# GBCART.net
KiCad netlist of a schematic drawn in EAGLE
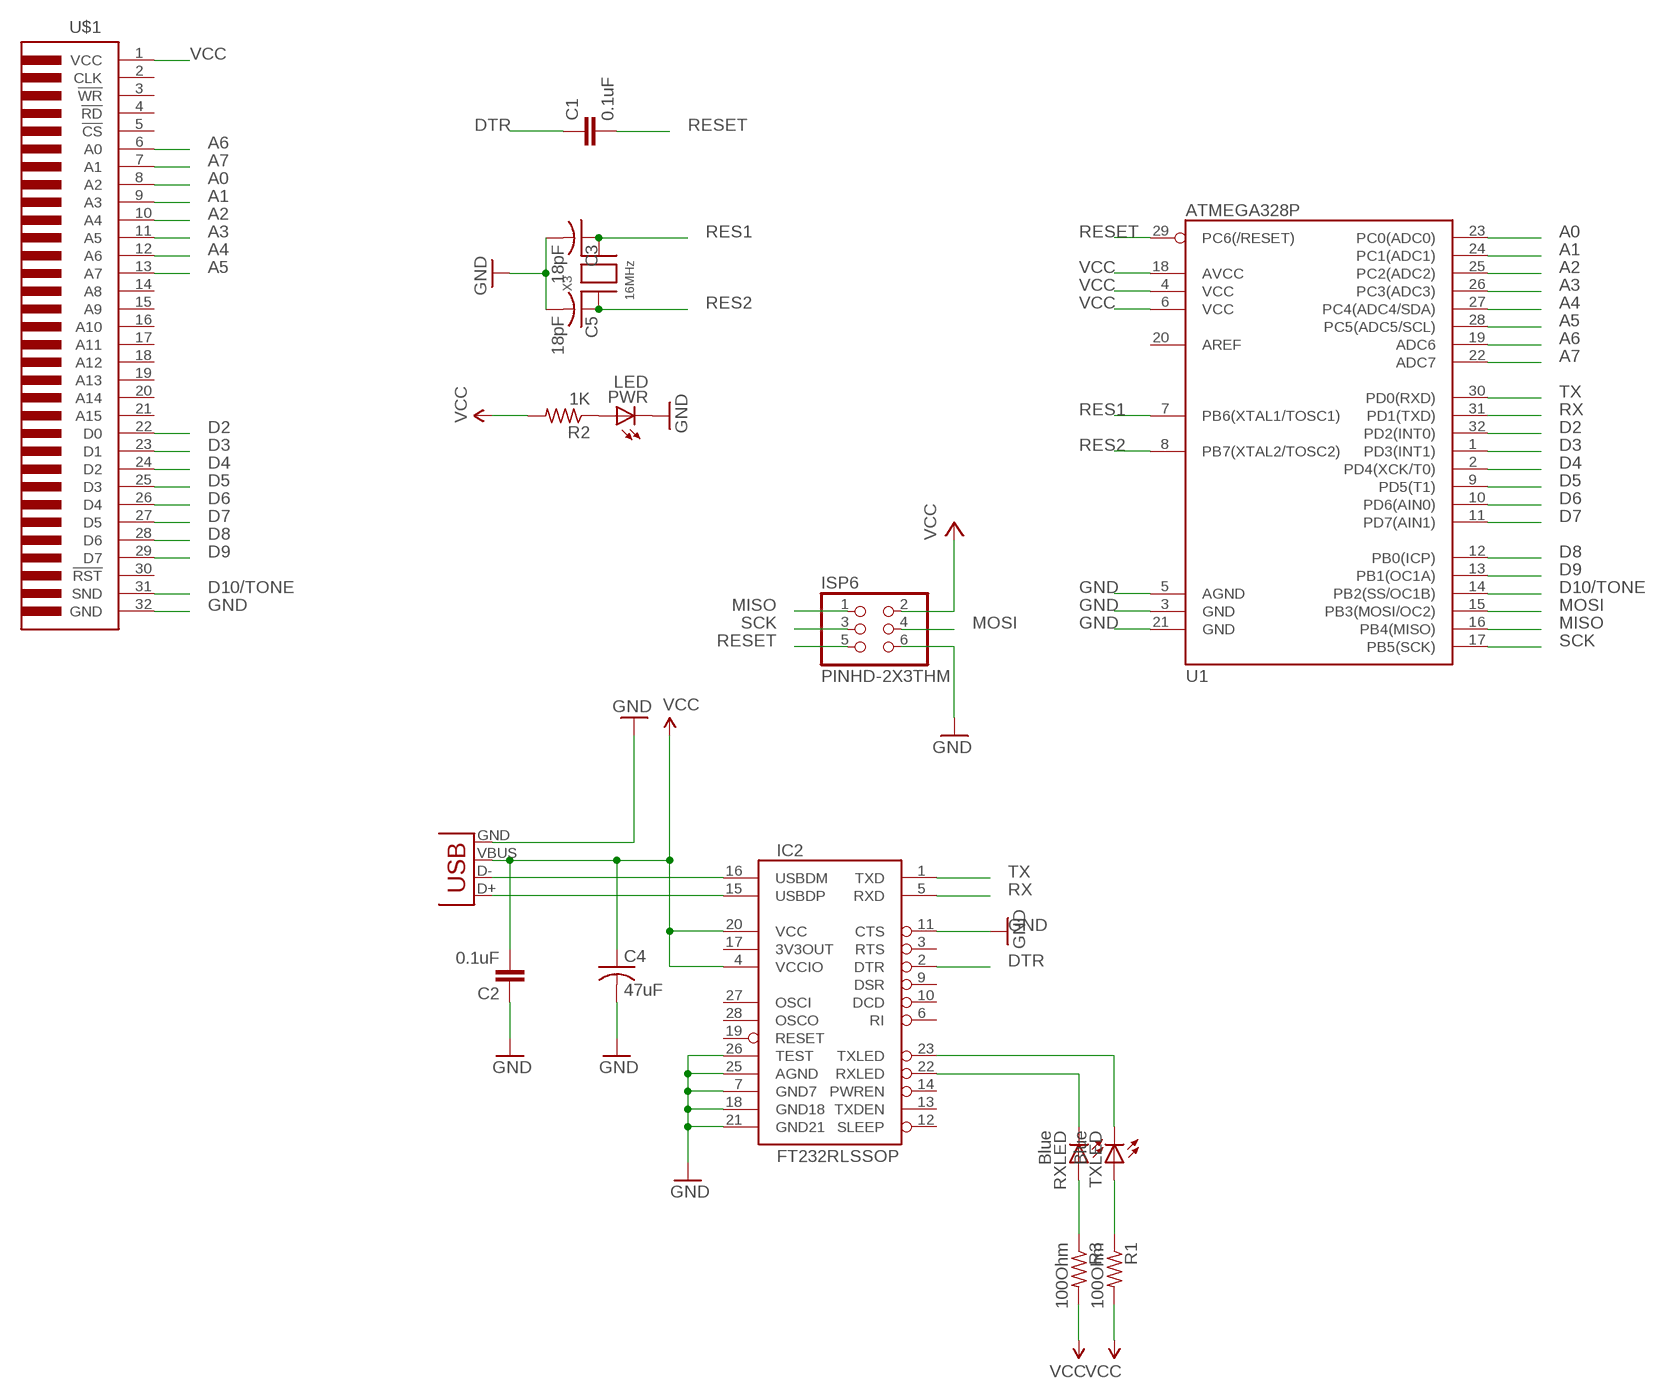
[diagram p0: schematic, sheet 1]

(export (version "E")
  (design (tool "Eeschema 10.0.6"))
  (components
    (comp (ref "C1")
      (value "0.1uF")
      (footprint "eagle-import:0805")
      (libsource (lib "eagle-import") (part "CAP0805"))
    )
    (comp (ref "C2")
      (value "0.1uF")
      (footprint "eagle-import:0805")
      (libsource (lib "eagle-import") (part "CAP0805"))
    )
    (comp (ref "C3")
      (value "18pF")
      (footprint "eagle-import:C0805K")
      (libsource (lib "eagle-import") (part "C-USC0805K"))
    )
    (comp (ref "C4")
      (value "47uF")
      (footprint "eagle-import:C0805")
      (libsource (lib "eagle-import") (part "rcl_C-USC0805"))
    )
    (comp (ref "C5")
      (value "18pF")
      (footprint "eagle-import:C0805K")
      (libsource (lib "eagle-import") (part "C-USC0805K"))
    )
    (comp (ref "IC2")
      (value "FT232RLSSOP")
      (footprint "eagle-import:SSOP28DB")
      (libsource (lib "eagle-import") (part "FT232RLSSOP"))
    )
    (comp (ref "ISP6")
      (value "PINHD-2X3THM")
      (footprint "eagle-import:ISP6")
      (libsource (lib "eagle-import") (part "PINHD-2X3THM"))
    )
    (comp (ref "PWR")
      (value "LED")
      (footprint "eagle-import:CHIPLED_0805")
      (libsource (lib "eagle-import") (part "LEDCHIPLED_0805"))
    )
    (comp (ref "R1")
      (value "100Ohm")
      (footprint "eagle-import:R0805")
      (libsource (lib "eagle-import") (part "R-US_R0805"))
    )
    (comp (ref "R2")
      (value "1K")
      (footprint "eagle-import:R0805")
      (libsource (lib "eagle-import") (part "R-US_R0805"))
    )
    (comp (ref "R3")
      (value "100Ohm")
      (footprint "eagle-import:R0805")
      (libsource (lib "eagle-import") (part "R-US_R0805"))
    )
    (comp (ref "RXLED")
      (value "Blue")
      (footprint "eagle-import:CHIPLED_0805")
      (libsource (lib "eagle-import") (part "led_LEDCHIPLED_0805"))
    )
    (comp (ref "TXLED")
      (value "Blue")
      (footprint "eagle-import:CHIPLED_0805")
      (libsource (lib "eagle-import") (part "led_LEDCHIPLED_0805"))
    )
    (comp (ref "U$1")
      (value "GBCART-FULL")
      (footprint "eagle-import:GBCART")
      (libsource (lib "eagle-import") (part "GBCART-FULL"))
    )
    (comp (ref "U1")
      (value "ATMEGA328P")
      (footprint "eagle-import:TQFP32-08")
      (libsource (lib "eagle-import") (part "ATMEGA168"))
    )
    (comp (ref "X1")
      (value "USBSMD")
      (footprint "eagle-import:USB-MINIB")
      (libsource (lib "eagle-import") (part "USBSMD"))
    )
    (comp (ref "X3")
      (value "16MHz")
      (footprint "eagle-import:NX5032")
      (libsource (lib "eagle-import") (part "XTALNX5032"))
    )
  )
  (nets
    (net (code "1") (name "/A0") (class "Default")
      (node (ref "U$1") (pin "8") (pinfunction "A2_8") (pintype "output"))
      (node (ref "U1") (pin "23") (pinfunction "PC0(ADC0)_23") (pintype "bidirectional"))
    )
    (net (code "2") (name "/A1") (class "Default")
      (node (ref "U$1") (pin "9") (pinfunction "A3_9") (pintype "output"))
      (node (ref "U1") (pin "24") (pinfunction "PC1(ADC1)_24") (pintype "bidirectional"))
    )
    (net (code "3") (name "/A2") (class "Default")
      (node (ref "U$1") (pin "10") (pinfunction "A4_10") (pintype "output"))
      (node (ref "U1") (pin "25") (pinfunction "PC2(ADC2)_25") (pintype "bidirectional"))
    )
    (net (code "4") (name "/A3") (class "Default")
      (node (ref "U$1") (pin "11") (pinfunction "A5_11") (pintype "output"))
      (node (ref "U1") (pin "26") (pinfunction "PC3(ADC3)_26") (pintype "bidirectional"))
    )
    (net (code "5") (name "/A4") (class "Default")
      (node (ref "U$1") (pin "12") (pinfunction "A6_12") (pintype "output"))
      (node (ref "U1") (pin "27") (pinfunction "PC4(ADC4/SDA)_27") (pintype "bidirectional"))
    )
    (net (code "6") (name "/A5") (class "Default")
      (node (ref "U$1") (pin "13") (pinfunction "A7_13") (pintype "output"))
      (node (ref "U1") (pin "28") (pinfunction "PC5(ADC5/SCL)_28") (pintype "bidirectional"))
    )
    (net (code "7") (name "/A6") (class "Default")
      (node (ref "U$1") (pin "6") (pinfunction "A0_6") (pintype "output"))
      (node (ref "U1") (pin "19") (pinfunction "ADC6_19") (pintype "bidirectional"))
    )
    (net (code "8") (name "/A7") (class "Default")
      (node (ref "U$1") (pin "7") (pinfunction "A1_7") (pintype "output"))
      (node (ref "U1") (pin "22") (pinfunction "ADC7_22") (pintype "bidirectional"))
    )
    (net (code "9") (name "/D2") (class "Default")
      (node (ref "U$1") (pin "22") (pinfunction "D0_22") (pintype "bidirectional"))
      (node (ref "U1") (pin "32") (pinfunction "PD2(INT0)_32") (pintype "bidirectional"))
    )
    (net (code "10") (name "/D3") (class "Default")
      (node (ref "U$1") (pin "23") (pinfunction "D1_23") (pintype "bidirectional"))
      (node (ref "U1") (pin "1") (pinfunction "PD3(INT1)_1") (pintype "bidirectional"))
    )
    (net (code "11") (name "/D4") (class "Default")
      (node (ref "U$1") (pin "24") (pinfunction "D2_24") (pintype "bidirectional"))
      (node (ref "U1") (pin "2") (pinfunction "PD4(XCK/T0)_2") (pintype "bidirectional"))
    )
    (net (code "12") (name "/D5") (class "Default")
      (node (ref "U$1") (pin "25") (pinfunction "D3_25") (pintype "bidirectional"))
      (node (ref "U1") (pin "9") (pinfunction "PD5(T1)_9") (pintype "bidirectional"))
    )
    (net (code "13") (name "/D6") (class "Default")
      (node (ref "U$1") (pin "26") (pinfunction "D4_26") (pintype "bidirectional"))
      (node (ref "U1") (pin "10") (pinfunction "PD6(AIN0)_10") (pintype "bidirectional"))
    )
    (net (code "14") (name "/D7") (class "Default")
      (node (ref "U$1") (pin "27") (pinfunction "D5_27") (pintype "bidirectional"))
      (node (ref "U1") (pin "11") (pinfunction "PD7(AIN1)_11") (pintype "bidirectional"))
    )
    (net (code "15") (name "/D8") (class "Default")
      (node (ref "U$1") (pin "28") (pinfunction "D6_28") (pintype "bidirectional"))
      (node (ref "U1") (pin "12") (pinfunction "PB0(ICP)_12") (pintype "bidirectional"))
    )
    (net (code "16") (name "/D9") (class "Default")
      (node (ref "U$1") (pin "29") (pinfunction "D7_29") (pintype "bidirectional"))
      (node (ref "U1") (pin "13") (pinfunction "PB1(OC1A)_13") (pintype "bidirectional"))
    )
    (net (code "17") (name "/D10{slash}TONE") (class "Default")
      (node (ref "U$1") (pin "31") (pinfunction "SND_31") (pintype "bidirectional"))
      (node (ref "U1") (pin "14") (pinfunction "PB2(SS/OC1B)_14") (pintype "bidirectional"))
    )
    (net (code "18") (name "/DTR") (class "Default")
      (node (ref "C1") (pin "1") (pinfunction "1_1") (pintype "passive"))
      (node (ref "IC2") (pin "2") (pinfunction "DTR_2") (pintype "output"))
    )
    (net (code "19") (name "/MISO") (class "Default")
      (node (ref "ISP6") (pin "1") (pinfunction "1_1") (pintype "passive"))
      (node (ref "U1") (pin "16") (pinfunction "PB4(MISO)_16") (pintype "bidirectional"))
    )
    (net (code "20") (name "/MOSI") (class "Default")
      (node (ref "ISP6") (pin "4") (pinfunction "4_4") (pintype "passive"))
      (node (ref "U1") (pin "15") (pinfunction "PB3(MOSI/OC2)_15") (pintype "bidirectional"))
    )
    (net (code "21") (name "/RES1") (class "Default")
      (node (ref "C3") (pin "1") (pinfunction "1_1") (pintype "passive"))
      (node (ref "U1") (pin "7") (pinfunction "PB6(XTAL1/TOSC1)_7") (pintype "bidirectional"))
      (node (ref "X3") (pin "P$2") (pinfunction "P$2_P$2") (pintype "bidirectional"))
    )
    (net (code "22") (name "/RES2") (class "Default")
      (node (ref "C5") (pin "1") (pinfunction "1_1") (pintype "passive"))
      (node (ref "U1") (pin "8") (pinfunction "PB7(XTAL2/TOSC2)_8") (pintype "bidirectional"))
      (node (ref "X3") (pin "P$1") (pinfunction "P$1_P$1") (pintype "bidirectional"))
    )
    (net (code "23") (name "/RESET") (class "Default")
      (node (ref "C1") (pin "2") (pinfunction "2_2") (pintype "passive"))
      (node (ref "ISP6") (pin "5") (pinfunction "5_5") (pintype "passive"))
      (node (ref "U1") (pin "29") (pinfunction "PC6(/RESET)_29") (pintype "bidirectional"))
    )
    (net (code "24") (name "/RX") (class "Default")
      (node (ref "IC2") (pin "5") (pinfunction "RXD_5") (pintype "input"))
      (node (ref "U1") (pin "31") (pinfunction "PD1(TXD)_31") (pintype "bidirectional"))
    )
    (net (code "25") (name "/SCK") (class "Default")
      (node (ref "ISP6") (pin "3") (pinfunction "3_3") (pintype "passive"))
      (node (ref "U1") (pin "17") (pinfunction "PB5(SCK)_17") (pintype "bidirectional"))
    )
    (net (code "26") (name "/TX") (class "Default")
      (node (ref "IC2") (pin "1") (pinfunction "TXD_1") (pintype "output"))
      (node (ref "U1") (pin "30") (pinfunction "PD0(RXD)_30") (pintype "bidirectional"))
    )
    (net (code "27") (name "GND") (class "Default")
      (node (ref "C2") (pin "1") (pinfunction "1_1") (pintype "passive"))
      (node (ref "C3") (pin "2") (pinfunction "2_2") (pintype "passive"))
      (node (ref "C4") (pin "2") (pinfunction "2_2") (pintype "passive"))
      (node (ref "C5") (pin "2") (pinfunction "2_2") (pintype "passive"))
      (node (ref "IC2") (pin "11") (pinfunction "CTS_11") (pintype "input"))
      (node (ref "IC2") (pin "18") (pinfunction "GND18_18") (pintype "power_in"))
      (node (ref "IC2") (pin "21") (pinfunction "GND21_21") (pintype "power_in"))
      (node (ref "IC2") (pin "25") (pinfunction "AGND_25") (pintype "power_in"))
      (node (ref "IC2") (pin "26") (pinfunction "TEST_26") (pintype "input"))
      (node (ref "IC2") (pin "7") (pinfunction "GND7_7") (pintype "power_in"))
      (node (ref "ISP6") (pin "6") (pinfunction "6_6") (pintype "passive"))
      (node (ref "PWR") (pin "C") (pinfunction "C_C") (pintype "passive"))
      (node (ref "U$1") (pin "32") (pinfunction "GND_32") (pintype "power_in"))
      (node (ref "U1") (pin "21") (pinfunction "GND_21") (pintype "bidirectional"))
      (node (ref "U1") (pin "3") (pinfunction "GND_3") (pintype "bidirectional"))
      (node (ref "U1") (pin "5") (pinfunction "AGND_5") (pintype "bidirectional"))
      (node (ref "X1") (pin "GND") (pinfunction "GND_GND") (pintype "bidirectional"))
    )
    (net (code "28") (name "Net-(IC2-RXLED)") (class "Default")
      (node (ref "IC2") (pin "22") (pinfunction "RXLED_22") (pintype "input"))
      (node (ref "RXLED") (pin "C") (pinfunction "C_C") (pintype "passive"))
    )
    (net (code "29") (name "Net-(IC2-TXLED)") (class "Default")
      (node (ref "IC2") (pin "23") (pinfunction "TXLED_23") (pintype "input"))
      (node (ref "TXLED") (pin "C") (pinfunction "C_C") (pintype "passive"))
    )
    (net (code "30") (name "Net-(IC2-USBDM)") (class "Default")
      (node (ref "IC2") (pin "16") (pinfunction "USBDM_16") (pintype "bidirectional"))
      (node (ref "X1") (pin "D-") (pinfunction "D-_D-") (pintype "bidirectional"))
    )
    (net (code "31") (name "Net-(IC2-USBDP)") (class "Default")
      (node (ref "IC2") (pin "15") (pinfunction "USBDP_15") (pintype "bidirectional"))
      (node (ref "X1") (pin "D+") (pinfunction "D+_D+") (pintype "bidirectional"))
    )
    (net (code "32") (name "Net-(PWR-PadA)") (class "Default")
      (node (ref "PWR") (pin "A") (pinfunction "A_A") (pintype "passive"))
      (node (ref "R2") (pin "1") (pinfunction "1_1") (pintype "passive"))
    )
    (net (code "33") (name "Net-(R1-Pad1)") (class "Default")
      (node (ref "R1") (pin "1") (pinfunction "1_1") (pintype "passive"))
      (node (ref "TXLED") (pin "A") (pinfunction "A_A") (pintype "passive"))
    )
    (net (code "34") (name "Net-(R3-Pad1)") (class "Default")
      (node (ref "R3") (pin "1") (pinfunction "1_1") (pintype "passive"))
      (node (ref "RXLED") (pin "A") (pinfunction "A_A") (pintype "passive"))
    )
    (net (code "35") (name "VCC") (class "Default")
      (node (ref "C2") (pin "2") (pinfunction "2_2") (pintype "passive"))
      (node (ref "C4") (pin "1") (pinfunction "1_1") (pintype "passive"))
      (node (ref "IC2") (pin "20") (pinfunction "VCC_20") (pintype "power_in"))
      (node (ref "IC2") (pin "4") (pinfunction "VCCIO_4") (pintype "power_in"))
      (node (ref "ISP6") (pin "2") (pinfunction "2_2") (pintype "passive"))
      (node (ref "R1") (pin "2") (pinfunction "2_2") (pintype "passive"))
      (node (ref "R2") (pin "2") (pinfunction "2_2") (pintype "passive"))
      (node (ref "R3") (pin "2") (pinfunction "2_2") (pintype "passive"))
      (node (ref "U$1") (pin "1") (pinfunction "VCC_1") (pintype "power_in"))
      (node (ref "U1") (pin "18") (pinfunction "AVCC_18") (pintype "bidirectional"))
      (node (ref "U1") (pin "4") (pinfunction "VCC_4") (pintype "bidirectional"))
      (node (ref "U1") (pin "6") (pinfunction "VCC_6") (pintype "bidirectional"))
      (node (ref "X1") (pin "VBUS") (pinfunction "VBUS_VBUS") (pintype "bidirectional"))
    )
    (net (code "36") (name "unconnected-(IC2-3V3OUT-Pad17)") (class "Default")
      (node (ref "IC2") (pin "17") (pinfunction "3V3OUT_17") (pintype "output"))
    )
    (net (code "37") (name "unconnected-(IC2-DCD-Pad10)") (class "Default")
      (node (ref "IC2") (pin "10") (pinfunction "DCD_10") (pintype "input"))
    )
    (net (code "38") (name "unconnected-(IC2-DSR-Pad9)") (class "Default")
      (node (ref "IC2") (pin "9") (pinfunction "DSR_9") (pintype "input"))
    )
    (net (code "39") (name "unconnected-(IC2-OSCI-Pad27)") (class "Default")
      (node (ref "IC2") (pin "27") (pinfunction "OSCI_27") (pintype "input"))
    )
    (net (code "40") (name "unconnected-(IC2-OSCO-Pad28)") (class "Default")
      (node (ref "IC2") (pin "28") (pinfunction "OSCO_28") (pintype "output"))
    )
    (net (code "41") (name "unconnected-(IC2-PWREN-Pad14)") (class "Default")
      (node (ref "IC2") (pin "14") (pinfunction "PWREN_14") (pintype "input"))
    )
    (net (code "42") (name "unconnected-(IC2-RESET-Pad19)") (class "Default")
      (node (ref "IC2") (pin "19") (pinfunction "RESET_19") (pintype "input"))
    )
    (net (code "43") (name "unconnected-(IC2-RI-Pad6)") (class "Default")
      (node (ref "IC2") (pin "6") (pinfunction "RI_6") (pintype "input"))
    )
    (net (code "44") (name "unconnected-(IC2-RTS-Pad3)") (class "Default")
      (node (ref "IC2") (pin "3") (pinfunction "RTS_3") (pintype "output"))
    )
    (net (code "45") (name "unconnected-(IC2-SLEEP-Pad12)") (class "Default")
      (node (ref "IC2") (pin "12") (pinfunction "SLEEP_12") (pintype "input"))
    )
    (net (code "46") (name "unconnected-(IC2-TXDEN-Pad13)") (class "Default")
      (node (ref "IC2") (pin "13") (pinfunction "TXDEN_13") (pintype "input"))
    )
    (net (code "47") (name "unconnected-(U$1-A8-Pad14)") (class "Default")
      (node (ref "U$1") (pin "14") (pinfunction "A8_14") (pintype "output"))
    )
    (net (code "48") (name "unconnected-(U$1-A9-Pad15)") (class "Default")
      (node (ref "U$1") (pin "15") (pinfunction "A9_15") (pintype "output"))
    )
    (net (code "49") (name "unconnected-(U$1-A10-Pad16)") (class "Default")
      (node (ref "U$1") (pin "16") (pinfunction "A10_16") (pintype "output"))
    )
    (net (code "50") (name "unconnected-(U$1-A11-Pad17)") (class "Default")
      (node (ref "U$1") (pin "17") (pinfunction "A11_17") (pintype "output"))
    )
    (net (code "51") (name "unconnected-(U$1-A12-Pad18)") (class "Default")
      (node (ref "U$1") (pin "18") (pinfunction "A12_18") (pintype "output"))
    )
    (net (code "52") (name "unconnected-(U$1-A13-Pad19)") (class "Default")
      (node (ref "U$1") (pin "19") (pinfunction "A13_19") (pintype "output"))
    )
    (net (code "53") (name "unconnected-(U$1-A14-Pad20)") (class "Default")
      (node (ref "U$1") (pin "20") (pinfunction "A14_20") (pintype "output"))
    )
    (net (code "54") (name "unconnected-(U$1-A15-Pad21)") (class "Default")
      (node (ref "U$1") (pin "21") (pinfunction "A15_21") (pintype "output"))
    )
    (net (code "55") (name "unconnected-(U$1-CLK-Pad2)") (class "Default")
      (node (ref "U$1") (pin "2") (pinfunction "CLK_2") (pintype "output"))
    )
    (net (code "56") (name "unconnected-(U$1-~{CS}-Pad5)") (class "Default")
      (node (ref "U$1") (pin "5") (pinfunction "~{CS}_5") (pintype "output"))
    )
    (net (code "57") (name "unconnected-(U$1-~{RD}-Pad4)") (class "Default")
      (node (ref "U$1") (pin "4") (pinfunction "~{RD}_4") (pintype "output"))
    )
    (net (code "58") (name "unconnected-(U$1-~{RST}-Pad30)") (class "Default")
      (node (ref "U$1") (pin "30") (pinfunction "~{RST}_30") (pintype "bidirectional"))
    )
    (net (code "59") (name "unconnected-(U$1-~{WR}-Pad3)") (class "Default")
      (node (ref "U$1") (pin "3") (pinfunction "~{WR}_3") (pintype "output"))
    )
    (net (code "60") (name "unconnected-(U1-AREF-Pad20)") (class "Default")
      (node (ref "U1") (pin "20") (pinfunction "AREF_20") (pintype "bidirectional"))
    )
  )
)
